# Sheet1.net
KiCad netlist of a schematic drawn in Altium Designer
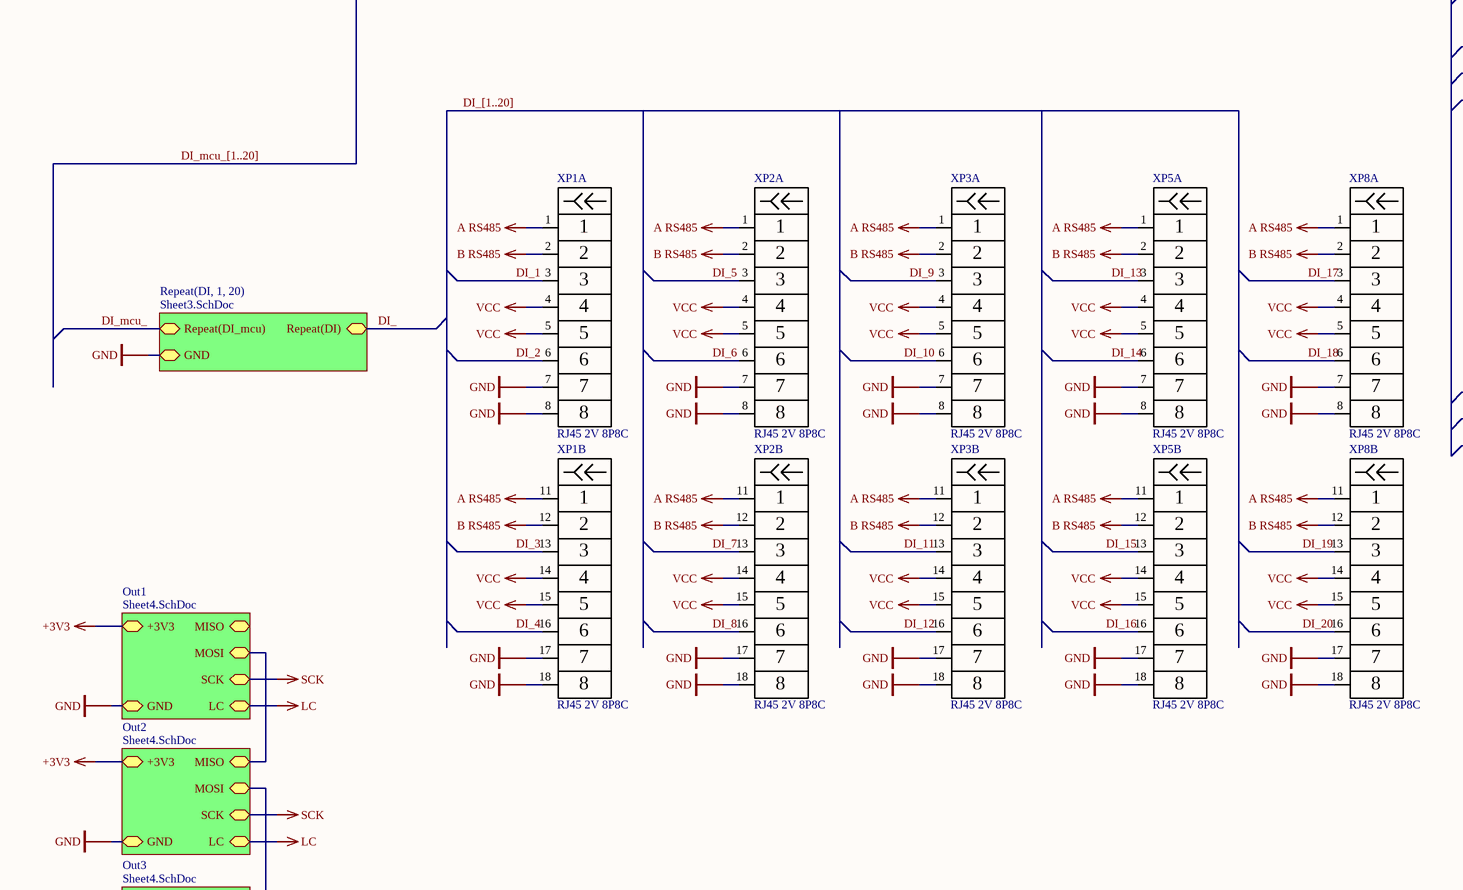
[diagram p0: Sheet1.SchDoc, top left]
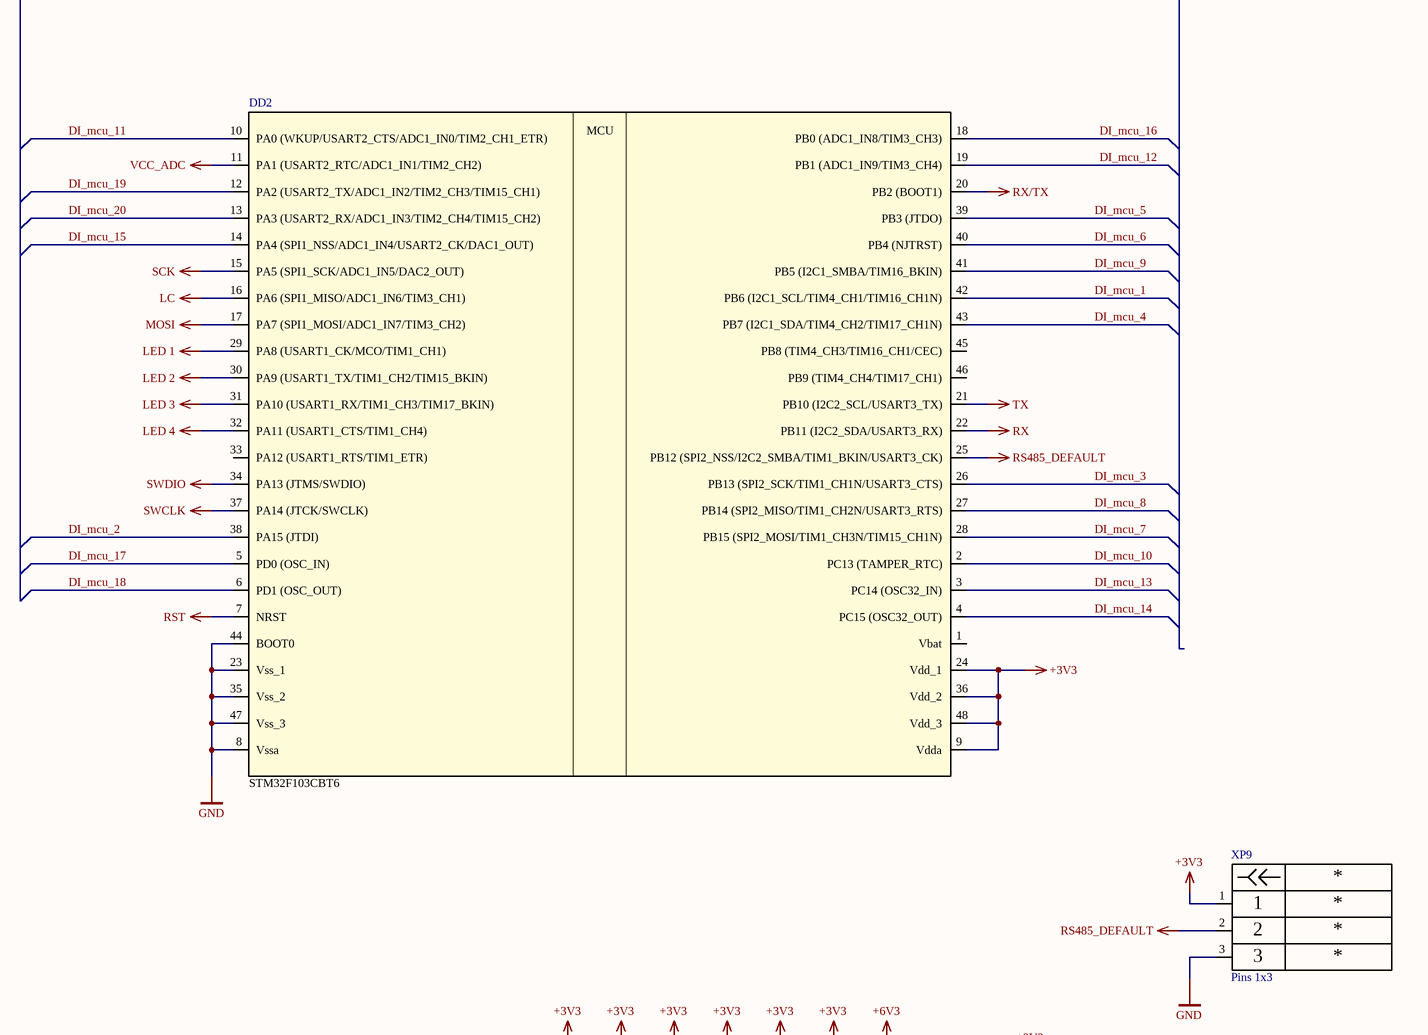
[diagram p1: Sheet1.SchDoc, top right]
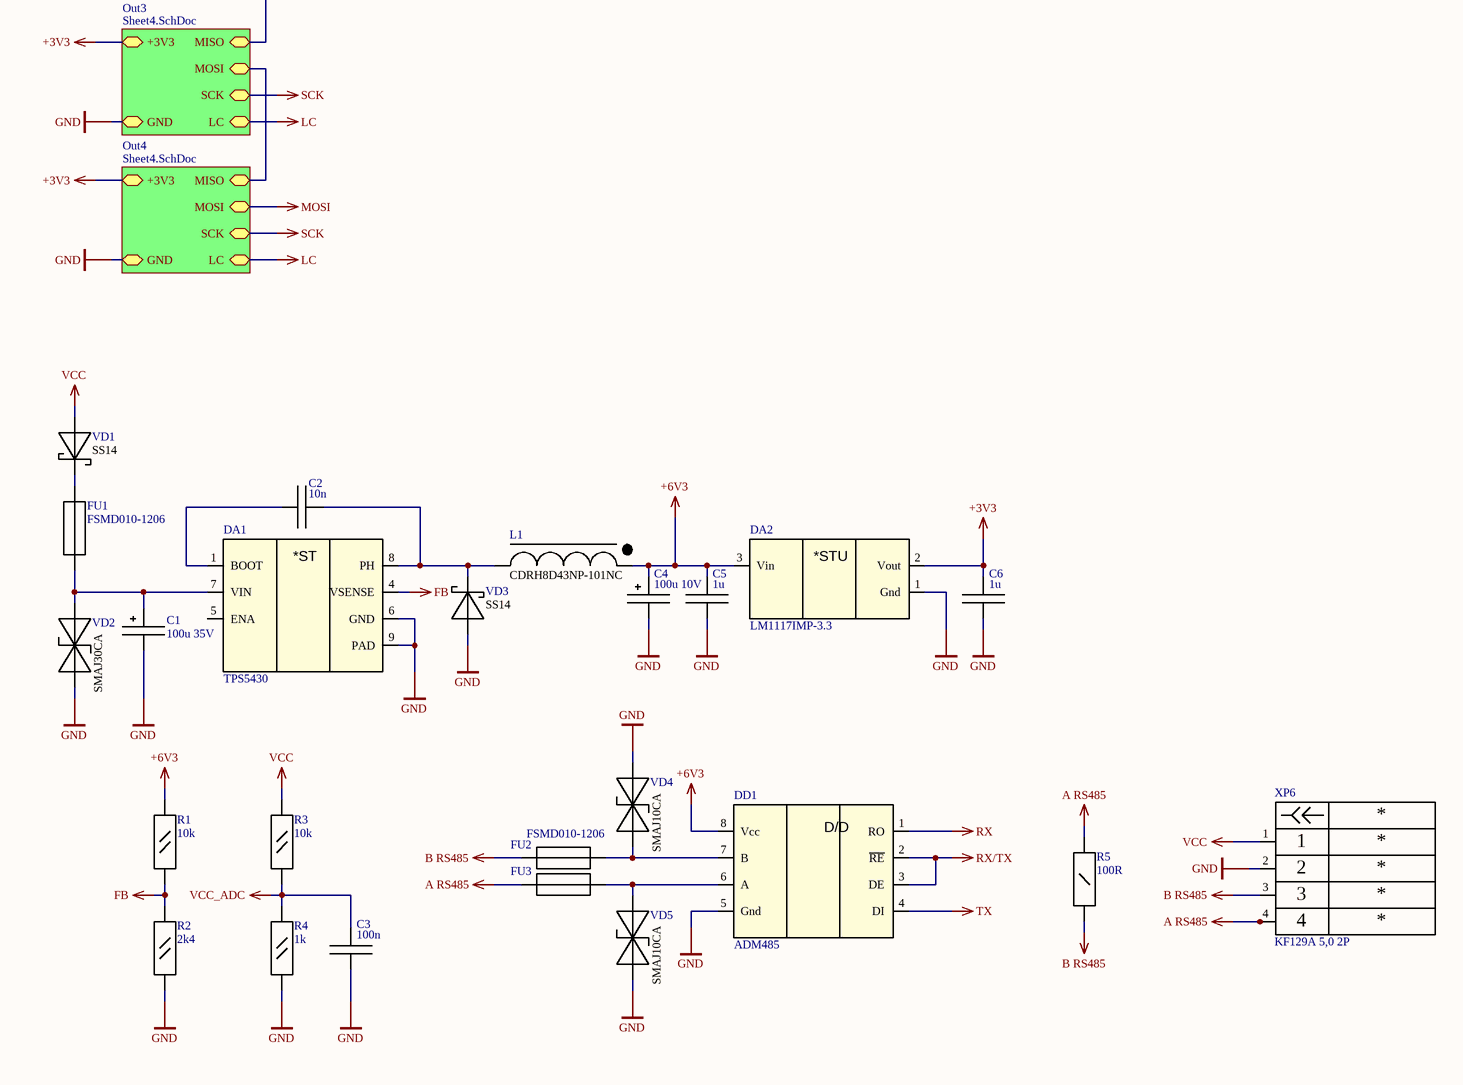
[diagram p2: Sheet1.SchDoc, bottom left]
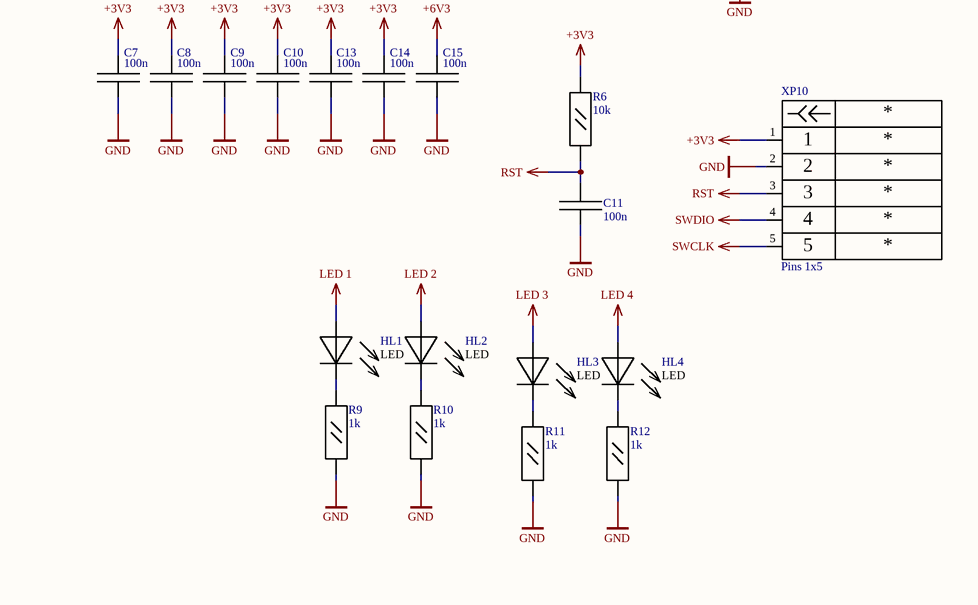
[diagram p3: Sheet1.SchDoc, bottom right]

(export (version "E")
  (design (tool "Eeschema 10.0.6"))
  (components
    (comp (ref "C1")
      (value "100u 35V")
      (footprint "Cap electro d6.3x2.54mm")
      (libsource (lib "Россыпь") (part "ECap"))
    )
    (comp (ref "C2") (value "10n") (footprint "Cap Ceramic 0805") (libsource (lib "Россыпь") (part "CerCap")))
    (comp (ref "C3")
      (value "100n")
      (footprint "Cap Ceramic 0805")
      (libsource (lib "Россыпь") (part "CerCap"))
    )
    (comp (ref "C4")
      (value "100u 10V")
      (footprint "Cap electro d6.3x2.54mm")
      (libsource (lib "Россыпь") (part "ECap"))
    )
    (comp (ref "C5") (value "1u") (footprint "Cap Ceramic 0805") (libsource (lib "Россыпь") (part "CerCap")))
    (comp (ref "C6") (value "1u") (footprint "Cap Ceramic 0805") (libsource (lib "Россыпь") (part "CerCap")))
    (comp (ref "C7")
      (value "100n")
      (footprint "Cap Ceramic 0805")
      (libsource (lib "Россыпь") (part "CerCap"))
    )
    (comp (ref "C8")
      (value "100n")
      (footprint "Cap Ceramic 0805")
      (libsource (lib "Россыпь") (part "CerCap"))
    )
    (comp (ref "C9")
      (value "100n")
      (footprint "Cap Ceramic 0805")
      (libsource (lib "Россыпь") (part "CerCap"))
    )
    (comp (ref "C10")
      (value "100n")
      (footprint "Cap Ceramic 0805")
      (libsource (lib "Россыпь") (part "CerCap"))
    )
    (comp (ref "C11")
      (value "100n")
      (footprint "Cap Ceramic 0805")
      (libsource (lib "Россыпь") (part "CerCap"))
    )
    (comp (ref "C13")
      (value "100n")
      (footprint "Cap Ceramic 0805")
      (libsource (lib "Россыпь") (part "CerCap"))
    )
    (comp (ref "C14")
      (value "100n")
      (footprint "Cap Ceramic 0805")
      (libsource (lib "Россыпь") (part "CerCap"))
    )
    (comp (ref "C15")
      (value "100n")
      (footprint "Cap Ceramic 0805")
      (libsource (lib "Россыпь") (part "CerCap"))
    )
    (comp (ref "DA1")
      (value "TPS5430")
      (footprint "SO8 S1.27W6.00 GP")
      (libsource (lib "Россыпь") (part "TPS5430"))
    )
    (comp (ref "DA2")
      (value "LM1117IMP-3.3")
      (footprint "SOT-232")
      (libsource (lib "Россыпь") (part "LM1117IMP-x.x"))
    )
    (comp (ref "DD1")
      (value "ADM485")
      (footprint "SO8 S1.27W6.00")
      (libsource (lib "Россыпь") (part "ADM485"))
    )
    (comp (ref "DD2")
      (value "STM32F103CBT6")
      (footprint "TQFP48 S0.5")
      (libsource (lib "Россыпь") (part "STM32F100C4T6"))
    )
    (comp (ref "FU1")
      (value "FSMD010-1206")
      (footprint "Fuse 1206")
      (libsource (lib "Россыпь") (part "FSMDxxx-1206"))
    )
    (comp (ref "FU2")
      (value "FSMD010-1206")
      (footprint "Fuse 1206")
      (libsource (lib "Россыпь") (part "FSMDxxx-1206"))
    )
    (comp (ref "FU3")
      (value "FSMD010-1206")
      (footprint "Fuse 1206")
      (libsource (lib "Россыпь") (part "FSMDxxx-1206"))
    )
    (comp (ref "HL1") (value "LED") (footprint "LED 0805") (libsource (lib "Россыпь") (part "LED")))
    (comp (ref "HL2") (value "LED") (footprint "LED 0805") (libsource (lib "Россыпь") (part "LED")))
    (comp (ref "HL3") (value "LED") (footprint "LED 0805") (libsource (lib "Россыпь") (part "LED")))
    (comp (ref "HL4") (value "LED") (footprint "LED 0805") (libsource (lib "Россыпь") (part "LED")))
    (comp (ref "L1")
      (value "CDRH8D43NP-101NC")
      (footprint "CDRH8D43NP-xxxNC")
      (libsource (lib "Россыпь") (part "CDRH8D43NP-xxxNC"))
    )
    (comp (ref "R1")
      (value "10k")
      (footprint "Resistor 0805")
      (libsource (lib "Россыпь") (part "Resistor 0,125W"))
    )
    (comp (ref "R2")
      (value "2k4")
      (footprint "Resistor 0805")
      (libsource (lib "Россыпь") (part "Resistor 0,125W"))
    )
    (comp (ref "R3")
      (value "10k")
      (footprint "Resistor 0805")
      (libsource (lib "Россыпь") (part "Resistor 0,125W"))
    )
    (comp (ref "R4")
      (value "1k")
      (footprint "Resistor 0805")
      (libsource (lib "Россыпь") (part "Resistor 0,125W"))
    )
    (comp (ref "R5")
      (value "100R")
      (footprint "Resistor 1206")
      (libsource (lib "Россыпь") (part "Resistor 0,25W"))
    )
    (comp (ref "R6")
      (value "10k")
      (footprint "Resistor 0805")
      (libsource (lib "Россыпь") (part "Resistor 0,125W"))
    )
    (comp (ref "R9")
      (value "1k")
      (footprint "Resistor 0805")
      (libsource (lib "Россыпь") (part "Resistor 0,125W"))
    )
    (comp (ref "R10")
      (value "1k")
      (footprint "Resistor 0805")
      (libsource (lib "Россыпь") (part "Resistor 0,125W"))
    )
    (comp (ref "R11")
      (value "1k")
      (footprint "Resistor 0805")
      (libsource (lib "Россыпь") (part "Resistor 0,125W"))
    )
    (comp (ref "R12")
      (value "1k")
      (footprint "Resistor 0805")
      (libsource (lib "Россыпь") (part "Resistor 0,125W"))
    )
    (comp (ref "VD1") (value "SS14") (footprint "DO-214AC SMA") (libsource (lib "Россыпь") (part "SS14")))
    (comp (ref "VD2")
      (value "SMAJ30CA")
      (footprint "DO-214AC SMA")
      (libsource (lib "Россыпь") (part "SMAJxxCA"))
    )
    (comp (ref "VD3") (value "SS14") (footprint "DO-214AC SMA") (libsource (lib "Россыпь") (part "SS14")))
    (comp (ref "VD4")
      (value "SMAJ10CA")
      (footprint "DO-214AC SMA")
      (libsource (lib "Россыпь") (part "SMAJxxCA"))
    )
    (comp (ref "VD5")
      (value "SMAJ10CA")
      (footprint "DO-214AC SMA")
      (libsource (lib "Россыпь") (part "SMAJxxCA"))
    )
    (comp (ref "XP1")
      (value "RJ45 2V 8P8C")
      (footprint "RJ45 2V 8P8C")
      (libsource (lib "Россыпь") (part "RJ45 2V 8P8C"))
    )
    (comp (ref "XP2")
      (value "RJ45 2V 8P8C")
      (footprint "RJ45 2V 8P8C")
      (libsource (lib "Россыпь") (part "RJ45 2V 8P8C"))
    )
    (comp (ref "XP3")
      (value "RJ45 2V 8P8C")
      (footprint "RJ45 2V 8P8C")
      (libsource (lib "Россыпь") (part "RJ45 2V 8P8C"))
    )
    (comp (ref "XP5")
      (value "RJ45 2V 8P8C")
      (footprint "RJ45 2V 8P8C")
      (libsource (lib "Россыпь") (part "RJ45 2V 8P8C"))
    )
    (comp (ref "XP6")
      (value "KF129A 5,0 2P")
      (footprint "KF129A 5,0 2P")
      (fields
        (field (name "NAME1") "*")
        (field (name "NAME2") "*")
        (field (name "NAME3") "*")
        (field (name "NAME") "*")
        (field (name "NAME4") "*")
      )
      (libsource (lib "Россыпь") (part "KF129A 5,0 2P"))
    )
    (comp (ref "XP8")
      (value "RJ45 2V 8P8C")
      (footprint "RJ45 2V 8P8C")
      (libsource (lib "Россыпь") (part "RJ45 2V 8P8C"))
    )
    (comp (ref "XP9")
      (value "Pins 1x3")
      (footprint "Pins 1x3")
      (fields
        (field (name "NAME1") "*")
        (field (name "NAME") "*")
        (field (name "NAME2") "*")
        (field (name "NAME3") "*")
      )
      (libsource (lib "Россыпь") (part "Pins 1x3"))
    )
    (comp (ref "XP10")
      (value "Pins 1x5")
      (footprint "Pins 1x5")
      (fields
        (field (name "NAME1") "*")
        (field (name "NAME") "*")
        (field (name "NAME2") "*")
        (field (name "NAME3") "*")
        (field (name "NAME4") "*")
        (field (name "NAME5") "*")
      )
      (libsource (lib "Россыпь") (part "Pins 1x5"))
    )
  )
  (nets
    (net (code "1") (name "+3V3") (class "Default")
      (node (ref "C10") (pin "2") (pinfunction "2_2") (pintype "passive"))
      (node (ref "C13") (pin "2") (pinfunction "2_2") (pintype "passive"))
      (node (ref "C14") (pin "2") (pinfunction "2_2") (pintype "passive"))
      (node (ref "C6") (pin "2") (pinfunction "2_2") (pintype "passive"))
      (node (ref "C7") (pin "2") (pinfunction "2_2") (pintype "passive"))
      (node (ref "C8") (pin "2") (pinfunction "2_2") (pintype "passive"))
      (node (ref "C9") (pin "2") (pinfunction "2_2") (pintype "passive"))
      (node (ref "DA2") (pin "2") (pinfunction "Vout_2") (pintype "passive"))
      (node (ref "DD2") (pin "24") (pinfunction "Vdd_1_24") (pintype "passive"))
      (node (ref "DD2") (pin "36") (pinfunction "Vdd_2_36") (pintype "passive"))
      (node (ref "DD2") (pin "48") (pinfunction "Vdd_3_48") (pintype "passive"))
      (node (ref "DD2") (pin "9") (pinfunction "Vdda_9") (pintype "passive"))
      (node (ref "R6") (pin "1") (pinfunction "1_1") (pintype "passive"))
      (node (ref "XP10") (pin "1") (pinfunction "1_1") (pintype "passive"))
      (node (ref "XP9") (pin "1") (pinfunction "1_1") (pintype "passive"))
    )
    (net (code "2") (name "+6V3") (class "Default")
      (node (ref "C15") (pin "2") (pinfunction "2_2") (pintype "passive"))
      (node (ref "C4") (pin "2") (pinfunction "2_2") (pintype "passive"))
      (node (ref "C5") (pin "2") (pinfunction "2_2") (pintype "passive"))
      (node (ref "DA2") (pin "3") (pinfunction "Vin_3") (pintype "passive"))
      (node (ref "DD1") (pin "8") (pinfunction "Vcc_8") (pintype "passive"))
      (node (ref "L1") (pin "1") (pinfunction "1_1") (pintype "passive"))
      (node (ref "R1") (pin "1") (pinfunction "1_1") (pintype "passive"))
    )
    (net (code "4") (name "/DI_1") (class "Default")
      (node (ref "XP1") (pin "3") (pinfunction "3_3") (pintype "passive"))
    )
    (net (code "5") (name "/DI_2") (class "Default")
      (node (ref "XP1") (pin "6") (pinfunction "6_6") (pintype "passive"))
    )
    (net (code "6") (name "/DI_3") (class "Default")
      (node (ref "XP1") (pin "13") (pinfunction "13_13") (pintype "passive"))
    )
    (net (code "7") (name "/DI_4") (class "Default")
      (node (ref "XP1") (pin "16") (pinfunction "16_16") (pintype "passive"))
    )
    (net (code "8") (name "/DI_5") (class "Default")
      (node (ref "XP2") (pin "3") (pinfunction "3_3") (pintype "passive"))
    )
    (net (code "9") (name "/DI_6") (class "Default")
      (node (ref "XP2") (pin "6") (pinfunction "6_6") (pintype "passive"))
    )
    (net (code "10") (name "/DI_7") (class "Default")
      (node (ref "XP2") (pin "13") (pinfunction "13_13") (pintype "passive"))
    )
    (net (code "11") (name "/DI_8") (class "Default")
      (node (ref "XP2") (pin "16") (pinfunction "16_16") (pintype "passive"))
    )
    (net (code "12") (name "/DI_9") (class "Default")
      (node (ref "XP3") (pin "3") (pinfunction "3_3") (pintype "passive"))
    )
    (net (code "13") (name "/DI_10") (class "Default")
      (node (ref "XP3") (pin "6") (pinfunction "6_6") (pintype "passive"))
    )
    (net (code "14") (name "/DI_11") (class "Default")
      (node (ref "XP3") (pin "13") (pinfunction "13_13") (pintype "passive"))
    )
    (net (code "15") (name "/DI_12") (class "Default")
      (node (ref "XP3") (pin "16") (pinfunction "16_16") (pintype "passive"))
    )
    (net (code "16") (name "/DI_13") (class "Default")
      (node (ref "XP5") (pin "3") (pinfunction "3_3") (pintype "passive"))
    )
    (net (code "17") (name "/DI_14") (class "Default")
      (node (ref "XP5") (pin "6") (pinfunction "6_6") (pintype "passive"))
    )
    (net (code "18") (name "/DI_15") (class "Default")
      (node (ref "XP5") (pin "13") (pinfunction "13_13") (pintype "passive"))
    )
    (net (code "19") (name "/DI_16") (class "Default")
      (node (ref "XP5") (pin "16") (pinfunction "16_16") (pintype "passive"))
    )
    (net (code "20") (name "/DI_17") (class "Default")
      (node (ref "XP8") (pin "3") (pinfunction "3_3") (pintype "passive"))
    )
    (net (code "21") (name "/DI_18") (class "Default")
      (node (ref "XP8") (pin "6") (pinfunction "6_6") (pintype "passive"))
    )
    (net (code "22") (name "/DI_19") (class "Default")
      (node (ref "XP8") (pin "13") (pinfunction "13_13") (pintype "passive"))
    )
    (net (code "23") (name "/DI_20") (class "Default")
      (node (ref "XP8") (pin "16") (pinfunction "16_16") (pintype "passive"))
    )
    (net (code "26") (name "/DI_mcu_1") (class "Default")
      (node (ref "DD2") (pin "42") (pinfunction "PB6_(I2C1_SCL/TIM4_CH1/TIM16_CH1N)_42") (pintype "passive"))
    )
    (net (code "27") (name "/DI_mcu_2") (class "Default")
      (node (ref "DD2") (pin "38") (pinfunction "PA15_(JTDI)_38") (pintype "passive"))
    )
    (net (code "28") (name "/DI_mcu_3") (class "Default")
      (node (ref "DD2") (pin "26") (pinfunction "PB13_(SPI2_SCK/TIM1_CH1N/USART3_CTS)_26") (pintype "passive"))
    )
    (net (code "29") (name "/DI_mcu_4") (class "Default")
      (node (ref "DD2") (pin "43") (pinfunction "PB7_(I2C1_SDA/TIM4_CH2/TIM17_CH1N)_43") (pintype "passive"))
    )
    (net (code "30") (name "/DI_mcu_5") (class "Default")
      (node (ref "DD2") (pin "39") (pinfunction "PB3_(JTDO)_39") (pintype "passive"))
    )
    (net (code "31") (name "/DI_mcu_6") (class "Default")
      (node (ref "DD2") (pin "40") (pinfunction "PB4_(NJTRST)_40") (pintype "passive"))
    )
    (net (code "32") (name "/DI_mcu_7") (class "Default")
      (node (ref "DD2") (pin "28") (pinfunction "PB15_(SPI2_MOSI/TIM1_CH3N/TIM15_CH1N)_28") (pintype "passive"))
    )
    (net (code "33") (name "/DI_mcu_8") (class "Default")
      (node (ref "DD2") (pin "27") (pinfunction "PB14_(SPI2_MISO/TIM1_CH2N/USART3_RTS)_27") (pintype "passive"))
    )
    (net (code "34") (name "/DI_mcu_9") (class "Default")
      (node (ref "DD2") (pin "41") (pinfunction "PB5_(I2C1_SMBA/TIM16_BKIN)_41") (pintype "passive"))
    )
    (net (code "35") (name "/DI_mcu_10") (class "Default")
      (node (ref "DD2") (pin "2") (pinfunction "PC13_(TAMPER_RTC)_2") (pintype "passive"))
    )
    (net (code "36") (name "/DI_mcu_11") (class "Default")
      (node (ref "DD2") (pin "10") (pinfunction "PA0_(WKUP/USART2_CTS/ADC1_IN0/TIM2_CH1_ETR)_10") (pintype "passive"))
    )
    (net (code "37") (name "/DI_mcu_12") (class "Default")
      (node (ref "DD2") (pin "19") (pinfunction "PB1_(ADC1_IN9/TIM3_CH4)_19") (pintype "passive"))
    )
    (net (code "38") (name "/DI_mcu_13") (class "Default")
      (node (ref "DD2") (pin "3") (pinfunction "PC14_(OSC32_IN)_3") (pintype "passive"))
    )
    (net (code "39") (name "/DI_mcu_14") (class "Default")
      (node (ref "DD2") (pin "4") (pinfunction "PC15_(OSC32_OUT)_4") (pintype "passive"))
    )
    (net (code "40") (name "/DI_mcu_15") (class "Default")
      (node (ref "DD2") (pin "14") (pinfunction "PA4_(SPI1_NSS/ADC1_IN4/USART2_CK/DAC1_OUT)_14") (pintype "passive"))
    )
    (net (code "41") (name "/DI_mcu_16") (class "Default")
      (node (ref "DD2") (pin "18") (pinfunction "PB0_(ADC1_IN8/TIM3_CH3)_18") (pintype "passive"))
    )
    (net (code "42") (name "/DI_mcu_17") (class "Default")
      (node (ref "DD2") (pin "5") (pinfunction "PD0_(OSC_IN)_5") (pintype "passive"))
    )
    (net (code "43") (name "/DI_mcu_18") (class "Default")
      (node (ref "DD2") (pin "6") (pinfunction "PD1_(OSC_OUT)_6") (pintype "passive"))
    )
    (net (code "44") (name "/DI_mcu_19") (class "Default")
      (node (ref "DD2") (pin "12") (pinfunction "PA2_(USART2_TX/ADC1_IN2/TIM2_CH3/TIM15_CH1)_12") (pintype "passive"))
    )
    (net (code "45") (name "/DI_mcu_20") (class "Default")
      (node (ref "DD2") (pin "13") (pinfunction "PA3_(USART2_RX/ADC1_IN3/TIM2_CH4/TIM15_CH2)_13") (pintype "passive"))
    )
    (net (code "51") (name "A RS485") (class "Default")
      (node (ref "FU3") (pin "1") (pinfunction "1_1") (pintype "passive"))
      (node (ref "R5") (pin "1") (pinfunction "1_1") (pintype "passive"))
      (node (ref "XP1") (pin "1") (pinfunction "1_1") (pintype "passive"))
      (node (ref "XP1") (pin "11") (pinfunction "11_11") (pintype "passive"))
      (node (ref "XP2") (pin "1") (pinfunction "1_1") (pintype "passive"))
      (node (ref "XP2") (pin "11") (pinfunction "11_11") (pintype "passive"))
      (node (ref "XP3") (pin "1") (pinfunction "1_1") (pintype "passive"))
      (node (ref "XP3") (pin "11") (pinfunction "11_11") (pintype "passive"))
      (node (ref "XP5") (pin "1") (pinfunction "1_1") (pintype "passive"))
      (node (ref "XP5") (pin "11") (pinfunction "11_11") (pintype "passive"))
      (node (ref "XP6") (pin "4") (pinfunction "4_4") (pintype "passive"))
      (node (ref "XP8") (pin "1") (pinfunction "1_1") (pintype "passive"))
      (node (ref "XP8") (pin "11") (pinfunction "11_11") (pintype "passive"))
    )
    (net (code "52") (name "B RS485") (class "Default")
      (node (ref "FU2") (pin "1") (pinfunction "1_1") (pintype "passive"))
      (node (ref "R5") (pin "2") (pinfunction "2_2") (pintype "passive"))
      (node (ref "XP1") (pin "12") (pinfunction "12_12") (pintype "passive"))
      (node (ref "XP1") (pin "2") (pinfunction "2_2") (pintype "passive"))
      (node (ref "XP2") (pin "12") (pinfunction "12_12") (pintype "passive"))
      (node (ref "XP2") (pin "2") (pinfunction "2_2") (pintype "passive"))
      (node (ref "XP3") (pin "12") (pinfunction "12_12") (pintype "passive"))
      (node (ref "XP3") (pin "2") (pinfunction "2_2") (pintype "passive"))
      (node (ref "XP5") (pin "12") (pinfunction "12_12") (pintype "passive"))
      (node (ref "XP5") (pin "2") (pinfunction "2_2") (pintype "passive"))
      (node (ref "XP6") (pin "3") (pinfunction "3_3") (pintype "passive"))
      (node (ref "XP8") (pin "12") (pinfunction "12_12") (pintype "passive"))
      (node (ref "XP8") (pin "2") (pinfunction "2_2") (pintype "passive"))
    )
    (net (code "53") (name "FB") (class "Default")
      (node (ref "DA1") (pin "4") (pinfunction "VSENSE_4") (pintype "passive"))
      (node (ref "R1") (pin "2") (pinfunction "2_2") (pintype "passive"))
      (node (ref "R2") (pin "1") (pinfunction "1_1") (pintype "passive"))
    )
    (net (code "54") (name "GND") (class "Default")
      (node (ref "C1") (pin "1") (pinfunction "1_1") (pintype "passive"))
      (node (ref "C10") (pin "1") (pinfunction "1_1") (pintype "passive"))
      (node (ref "C11") (pin "1") (pinfunction "1_1") (pintype "passive"))
      (node (ref "C13") (pin "1") (pinfunction "1_1") (pintype "passive"))
      (node (ref "C14") (pin "1") (pinfunction "1_1") (pintype "passive"))
      (node (ref "C15") (pin "1") (pinfunction "1_1") (pintype "passive"))
      (node (ref "C3") (pin "1") (pinfunction "1_1") (pintype "passive"))
      (node (ref "C4") (pin "1") (pinfunction "1_1") (pintype "passive"))
      (node (ref "C5") (pin "1") (pinfunction "1_1") (pintype "passive"))
      (node (ref "C6") (pin "1") (pinfunction "1_1") (pintype "passive"))
      (node (ref "C7") (pin "1") (pinfunction "1_1") (pintype "passive"))
      (node (ref "C8") (pin "1") (pinfunction "1_1") (pintype "passive"))
      (node (ref "C9") (pin "1") (pinfunction "1_1") (pintype "passive"))
      (node (ref "DA1") (pin "6") (pinfunction "GND_6") (pintype "passive"))
      (node (ref "DA1") (pin "9") (pinfunction "PAD_9") (pintype "passive"))
      (node (ref "DA2") (pin "1") (pinfunction "Gnd_1") (pintype "passive"))
      (node (ref "DD1") (pin "5") (pinfunction "Gnd_5") (pintype "passive"))
      (node (ref "DD2") (pin "23") (pinfunction "Vss_1_23") (pintype "passive"))
      (node (ref "DD2") (pin "35") (pinfunction "Vss_2_35") (pintype "passive"))
      (node (ref "DD2") (pin "44") (pinfunction "BOOT0_44") (pintype "passive"))
      (node (ref "DD2") (pin "47") (pinfunction "Vss_3_47") (pintype "passive"))
      (node (ref "DD2") (pin "8") (pinfunction "Vssa_8") (pintype "passive"))
      (node (ref "R10") (pin "2") (pinfunction "2_2") (pintype "passive"))
      (node (ref "R11") (pin "2") (pinfunction "2_2") (pintype "passive"))
      (node (ref "R12") (pin "2") (pinfunction "2_2") (pintype "passive"))
      (node (ref "R2") (pin "2") (pinfunction "2_2") (pintype "passive"))
      (node (ref "R4") (pin "2") (pinfunction "2_2") (pintype "passive"))
      (node (ref "R9") (pin "2") (pinfunction "2_2") (pintype "passive"))
      (node (ref "VD2") (pin "1") (pinfunction "1_1") (pintype "passive"))
      (node (ref "VD3") (pin "1") (pinfunction "A_1") (pintype "passive"))
      (node (ref "VD4") (pin "1") (pinfunction "1_1") (pintype "passive"))
      (node (ref "VD5") (pin "1") (pinfunction "1_1") (pintype "passive"))
      (node (ref "XP1") (pin "17") (pinfunction "17_17") (pintype "passive"))
      (node (ref "XP1") (pin "18") (pinfunction "18_18") (pintype "passive"))
      (node (ref "XP1") (pin "7") (pinfunction "7_7") (pintype "passive"))
      (node (ref "XP1") (pin "8") (pinfunction "8_8") (pintype "passive"))
      (node (ref "XP10") (pin "2") (pinfunction "2_2") (pintype "passive"))
      (node (ref "XP2") (pin "17") (pinfunction "17_17") (pintype "passive"))
      (node (ref "XP2") (pin "18") (pinfunction "18_18") (pintype "passive"))
      (node (ref "XP2") (pin "7") (pinfunction "7_7") (pintype "passive"))
      (node (ref "XP2") (pin "8") (pinfunction "8_8") (pintype "passive"))
      (node (ref "XP3") (pin "17") (pinfunction "17_17") (pintype "passive"))
      (node (ref "XP3") (pin "18") (pinfunction "18_18") (pintype "passive"))
      (node (ref "XP3") (pin "7") (pinfunction "7_7") (pintype "passive"))
      (node (ref "XP3") (pin "8") (pinfunction "8_8") (pintype "passive"))
      (node (ref "XP5") (pin "17") (pinfunction "17_17") (pintype "passive"))
      (node (ref "XP5") (pin "18") (pinfunction "18_18") (pintype "passive"))
      (node (ref "XP5") (pin "7") (pinfunction "7_7") (pintype "passive"))
      (node (ref "XP5") (pin "8") (pinfunction "8_8") (pintype "passive"))
      (node (ref "XP6") (pin "2") (pinfunction "2_2") (pintype "passive"))
      (node (ref "XP8") (pin "17") (pinfunction "17_17") (pintype "passive"))
      (node (ref "XP8") (pin "18") (pinfunction "18_18") (pintype "passive"))
      (node (ref "XP8") (pin "7") (pinfunction "7_7") (pintype "passive"))
      (node (ref "XP8") (pin "8") (pinfunction "8_8") (pintype "passive"))
      (node (ref "XP9") (pin "3") (pinfunction "3_3") (pintype "passive"))
    )
    (net (code "55") (name "LC") (class "Default")
      (node (ref "DD2") (pin "16") (pinfunction "PA6_(SPI1_MISO/ADC1_IN6/TIM3_CH1)_16") (pintype "passive"))
    )
    (net (code "56") (name "LED 1") (class "Default")
      (node (ref "DD2") (pin "29") (pinfunction "PA8_(USART1_CK/MCO/TIM1_CH1)_29") (pintype "passive"))
      (node (ref "HL1") (pin "1") (pinfunction "A_1") (pintype "passive"))
    )
    (net (code "57") (name "LED 2") (class "Default")
      (node (ref "DD2") (pin "30") (pinfunction "PA9_(USART1_TX/TIM1_CH2/TIM15_BKIN)_30") (pintype "passive"))
      (node (ref "HL2") (pin "1") (pinfunction "A_1") (pintype "passive"))
    )
    (net (code "58") (name "LED 3") (class "Default")
      (node (ref "DD2") (pin "31") (pinfunction "PA10_(USART1_RX/TIM1_CH3/TIM17_BKIN)_31") (pintype "passive"))
      (node (ref "HL3") (pin "1") (pinfunction "A_1") (pintype "passive"))
    )
    (net (code "59") (name "LED 4") (class "Default")
      (node (ref "DD2") (pin "32") (pinfunction "PA11_(USART1_CTS/TIM1_CH4)_32") (pintype "passive"))
      (node (ref "HL4") (pin "1") (pinfunction "A_1") (pintype "passive"))
    )
    (net (code "60") (name "MOSI") (class "Default")
      (node (ref "DD2") (pin "17") (pinfunction "PA7_(SPI1_MOSI/ADC1_IN7/TIM3_CH2)_17") (pintype "passive"))
    )
    (net (code "61") (name "Net-(DA1-BOOT)") (class "Default")
      (node (ref "C2") (pin "1") (pinfunction "1_1") (pintype "passive"))
      (node (ref "DA1") (pin "1") (pinfunction "BOOT_1") (pintype "passive"))
    )
    (net (code "62") (name "Net-(DA1-PH)") (class "Default")
      (node (ref "C2") (pin "2") (pinfunction "2_2") (pintype "passive"))
      (node (ref "DA1") (pin "8") (pinfunction "PH_8") (pintype "passive"))
      (node (ref "L1") (pin "2") (pinfunction "2_2") (pintype "passive"))
      (node (ref "VD3") (pin "2") (pinfunction "K_2") (pintype "passive"))
    )
    (net (code "63") (name "Net-(DA1-VIN)") (class "Default")
      (node (ref "C1") (pin "2") (pinfunction "2_2") (pintype "passive"))
      (node (ref "DA1") (pin "7") (pinfunction "VIN_7") (pintype "passive"))
      (node (ref "FU1") (pin "2") (pinfunction "2_2") (pintype "passive"))
      (node (ref "VD2") (pin "2") (pinfunction "2_2") (pintype "passive"))
    )
    (net (code "64") (name "Net-(DD1-A)") (class "Default")
      (node (ref "DD1") (pin "6") (pinfunction "A_6") (pintype "passive"))
      (node (ref "FU3") (pin "2") (pinfunction "2_2") (pintype "passive"))
      (node (ref "VD5") (pin "2") (pinfunction "2_2") (pintype "passive"))
    )
    (net (code "65") (name "Net-(DD1-B)") (class "Default")
      (node (ref "DD1") (pin "7") (pinfunction "B_7") (pintype "passive"))
      (node (ref "FU2") (pin "2") (pinfunction "2_2") (pintype "passive"))
      (node (ref "VD4") (pin "2") (pinfunction "2_2") (pintype "passive"))
    )
    (net (code "66") (name "Net-(HL1-K)") (class "Default")
      (node (ref "HL1") (pin "2") (pinfunction "K_2") (pintype "passive"))
      (node (ref "R9") (pin "1") (pinfunction "1_1") (pintype "passive"))
    )
    (net (code "67") (name "Net-(HL2-K)") (class "Default")
      (node (ref "HL2") (pin "2") (pinfunction "K_2") (pintype "passive"))
      (node (ref "R10") (pin "1") (pinfunction "1_1") (pintype "passive"))
    )
    (net (code "68") (name "Net-(HL3-K)") (class "Default")
      (node (ref "HL3") (pin "2") (pinfunction "K_2") (pintype "passive"))
      (node (ref "R11") (pin "1") (pinfunction "1_1") (pintype "passive"))
    )
    (net (code "69") (name "Net-(HL4-K)") (class "Default")
      (node (ref "HL4") (pin "2") (pinfunction "K_2") (pintype "passive"))
      (node (ref "R12") (pin "1") (pinfunction "1_1") (pintype "passive"))
    )
    (net (code "70") (name "Net-(VD1-K)") (class "Default")
      (node (ref "FU1") (pin "1") (pinfunction "1_1") (pintype "passive"))
      (node (ref "VD1") (pin "2") (pinfunction "K_2") (pintype "passive"))
    )
    (net (code "71") (name "RS485_DEFAULT") (class "Default")
      (node (ref "DD2") (pin "25") (pinfunction "PB12_(SPI2_NSS/I2C2_SMBA/TIM1_BKIN/USART3_CK)_25") (pintype "passive"))
      (node (ref "XP9") (pin "2") (pinfunction "2_2") (pintype "passive"))
    )
    (net (code "72") (name "RST") (class "Default")
      (node (ref "C11") (pin "2") (pinfunction "2_2") (pintype "passive"))
      (node (ref "DD2") (pin "7") (pinfunction "NRST_7") (pintype "passive"))
      (node (ref "R6") (pin "2") (pinfunction "2_2") (pintype "passive"))
      (node (ref "XP10") (pin "3") (pinfunction "3_3") (pintype "passive"))
    )
    (net (code "73") (name "RX") (class "Default")
      (node (ref "DD1") (pin "1") (pinfunction "RO_1") (pintype "passive"))
      (node (ref "DD2") (pin "22") (pinfunction "PB11_(I2C2_SDA/USART3_RX)_22") (pintype "passive"))
    )
    (net (code "74") (name "RX{slash}TX") (class "Default")
      (node (ref "DD1") (pin "2") (pinfunction "RE_2") (pintype "passive"))
      (node (ref "DD1") (pin "3") (pinfunction "DE_3") (pintype "passive"))
      (node (ref "DD2") (pin "20") (pinfunction "PB2_(BOOT1)_20") (pintype "passive"))
    )
    (net (code "75") (name "SCK") (class "Default")
      (node (ref "DD2") (pin "15") (pinfunction "PA5_(SPI1_SCK/ADC1_IN5/DAC2_OUT)_15") (pintype "passive"))
    )
    (net (code "76") (name "SWCLK") (class "Default")
      (node (ref "DD2") (pin "37") (pinfunction "PA14_(JTCK/SWCLK)_37") (pintype "passive"))
      (node (ref "XP10") (pin "5") (pinfunction "5_5") (pintype "passive"))
    )
    (net (code "77") (name "SWDIO") (class "Default")
      (node (ref "DD2") (pin "34") (pinfunction "PA13_(JTMS/SWDIO)_34") (pintype "passive"))
      (node (ref "XP10") (pin "4") (pinfunction "4_4") (pintype "passive"))
    )
    (net (code "78") (name "TX") (class "Default")
      (node (ref "DD1") (pin "4") (pinfunction "DI_4") (pintype "passive"))
      (node (ref "DD2") (pin "21") (pinfunction "PB10_(I2C2_SCL/USART3_TX)_21") (pintype "passive"))
    )
    (net (code "79") (name "VCC") (class "Default")
      (node (ref "R3") (pin "1") (pinfunction "1_1") (pintype "passive"))
      (node (ref "VD1") (pin "1") (pinfunction "A_1") (pintype "passive"))
      (node (ref "XP1") (pin "14") (pinfunction "14_14") (pintype "passive"))
      (node (ref "XP1") (pin "15") (pinfunction "15_15") (pintype "passive"))
      (node (ref "XP1") (pin "4") (pinfunction "4_4") (pintype "passive"))
      (node (ref "XP1") (pin "5") (pinfunction "5_5") (pintype "passive"))
      (node (ref "XP2") (pin "14") (pinfunction "14_14") (pintype "passive"))
      (node (ref "XP2") (pin "15") (pinfunction "15_15") (pintype "passive"))
      (node (ref "XP2") (pin "4") (pinfunction "4_4") (pintype "passive"))
      (node (ref "XP2") (pin "5") (pinfunction "5_5") (pintype "passive"))
      (node (ref "XP3") (pin "14") (pinfunction "14_14") (pintype "passive"))
      (node (ref "XP3") (pin "15") (pinfunction "15_15") (pintype "passive"))
      (node (ref "XP3") (pin "4") (pinfunction "4_4") (pintype "passive"))
      (node (ref "XP3") (pin "5") (pinfunction "5_5") (pintype "passive"))
      (node (ref "XP5") (pin "14") (pinfunction "14_14") (pintype "passive"))
      (node (ref "XP5") (pin "15") (pinfunction "15_15") (pintype "passive"))
      (node (ref "XP5") (pin "4") (pinfunction "4_4") (pintype "passive"))
      (node (ref "XP5") (pin "5") (pinfunction "5_5") (pintype "passive"))
      (node (ref "XP6") (pin "1") (pinfunction "1_1") (pintype "passive"))
      (node (ref "XP8") (pin "14") (pinfunction "14_14") (pintype "passive"))
      (node (ref "XP8") (pin "15") (pinfunction "15_15") (pintype "passive"))
      (node (ref "XP8") (pin "4") (pinfunction "4_4") (pintype "passive"))
      (node (ref "XP8") (pin "5") (pinfunction "5_5") (pintype "passive"))
    )
    (net (code "80") (name "VCC_ADC") (class "Default")
      (node (ref "C3") (pin "2") (pinfunction "2_2") (pintype "passive"))
      (node (ref "DD2") (pin "11") (pinfunction "PA1_(USART2_RTC/ADC1_IN1/TIM2_CH2)_11") (pintype "passive"))
      (node (ref "R3") (pin "2") (pinfunction "2_2") (pintype "passive"))
      (node (ref "R4") (pin "1") (pinfunction "1_1") (pintype "passive"))
    )
    (net (code "81") (name "unconnected-(DA1-ENA-Pad5)") (class "Default")
      (node (ref "DA1") (pin "5") (pinfunction "ENA_5") (pintype "passive"))
    )
    (net (code "82") (name "unconnected-(DA1-NC-Pad2)") (class "Default")
      (node (ref "DA1") (pin "2") (pinfunction "NC_2") (pintype "passive"))
    )
    (net (code "83") (name "unconnected-(DA1-NC-Pad3)") (class "Default")
      (node (ref "DA1") (pin "3") (pinfunction "NC_3") (pintype "passive"))
    )
    (net (code "84") (name "unconnected-(DD2-PA12_(USART1_RTS{slash}TIM1_ETR)-Pad33)") (class "Default")
      (node (ref "DD2") (pin "33") (pinfunction "PA12_(USART1_RTS/TIM1_ETR)_33") (pintype "passive"))
    )
    (net (code "85") (name "unconnected-(DD2-PB8_(TIM4_CH3{slash}TIM16_CH1{slash}CEC)-Pad45)") (class "Default")
      (node (ref "DD2") (pin "45") (pinfunction "PB8_(TIM4_CH3/TIM16_CH1/CEC)_45") (pintype "passive"))
    )
    (net (code "86") (name "unconnected-(DD2-PB9_(TIM4_CH4{slash}TIM17_CH1)-Pad46)") (class "Default")
      (node (ref "DD2") (pin "46") (pinfunction "PB9_(TIM4_CH4/TIM17_CH1)_46") (pintype "passive"))
    )
    (net (code "87") (name "unconnected-(DD2-Vbat-Pad1)") (class "Default")
      (node (ref "DD2") (pin "1") (pinfunction "Vbat_1") (pintype "passive"))
    )
  )
)
